# slave.net
KiCad netlist of a schematic drawn in EAGLE
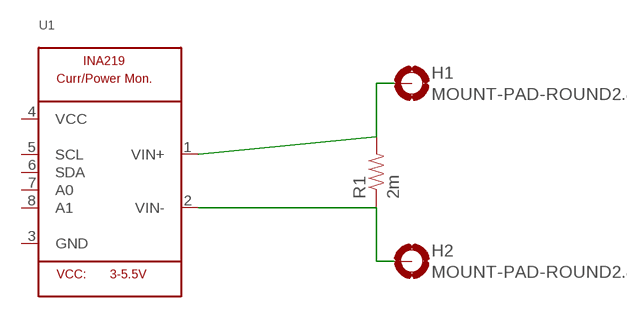
[diagram p0: schematic, sheet 1]

(export (version "E")
  (design (tool "Eeschema 10.0.6"))
  (components
    (comp (ref "H1")
      (value "MOUNT-PAD-ROUND2.8")
      (footprint "eagle-import:2,8-PAD")
      (libsource (lib "eagle-import") (part "MOUNT-PAD-ROUND2.8"))
    )
    (comp (ref "H2")
      (value "MOUNT-PAD-ROUND2.8")
      (footprint "eagle-import:2,8-PAD")
      (libsource (lib "eagle-import") (part "MOUNT-PAD-ROUND2.8"))
    )
    (comp (ref "R1")
      (value "2m")
      (footprint "eagle-import:R2512")
      (libsource (lib "eagle-import") (part "RESISTOR2512"))
    )
    (comp (ref "U1")
      (value "INA219")
      (footprint "eagle-import:SOT23-8")
      (libsource (lib "eagle-import") (part "INA219"))
    )
  )
  (nets
    (net (code "1") (name "Net-(H1-MOUNT)") (class "Default")
      (node (ref "H1") (pin "B2,8") (pinfunction "MOUNT_B2,8") (pintype "passive"))
      (node (ref "R1") (pin "2") (pinfunction "2_2") (pintype "passive"))
      (node (ref "U1") (pin "1") (pinfunction "VIN+_1") (pintype "bidirectional"))
    )
    (net (code "2") (name "Net-(H2-MOUNT)") (class "Default")
      (node (ref "H2") (pin "B2,8") (pinfunction "MOUNT_B2,8") (pintype "passive"))
      (node (ref "R1") (pin "1") (pinfunction "1_1") (pintype "passive"))
      (node (ref "U1") (pin "2") (pinfunction "VIN-_2") (pintype "bidirectional"))
    )
    (net (code "3") (name "unconnected-(U1-A0-Pad7)") (class "Default")
      (node (ref "U1") (pin "7") (pinfunction "A0_7") (pintype "bidirectional"))
    )
    (net (code "4") (name "unconnected-(U1-A1-Pad8)") (class "Default")
      (node (ref "U1") (pin "8") (pinfunction "A1_8") (pintype "bidirectional"))
    )
    (net (code "5") (name "unconnected-(U1-GND-Pad3)") (class "Default")
      (node (ref "U1") (pin "3") (pinfunction "GND_3") (pintype "bidirectional"))
    )
    (net (code "6") (name "unconnected-(U1-SCL-Pad5)") (class "Default")
      (node (ref "U1") (pin "5") (pinfunction "SCL_5") (pintype "bidirectional"))
    )
    (net (code "7") (name "unconnected-(U1-SDA-Pad6)") (class "Default")
      (node (ref "U1") (pin "6") (pinfunction "SDA_6") (pintype "bidirectional"))
    )
    (net (code "8") (name "unconnected-(U1-VCC-Pad4)") (class "Default")
      (node (ref "U1") (pin "4") (pinfunction "VCC_4") (pintype "bidirectional"))
    )
  )
)
